# uTCA_Tongue3.net
KiCad netlist of a schematic drawn in Altium Designer
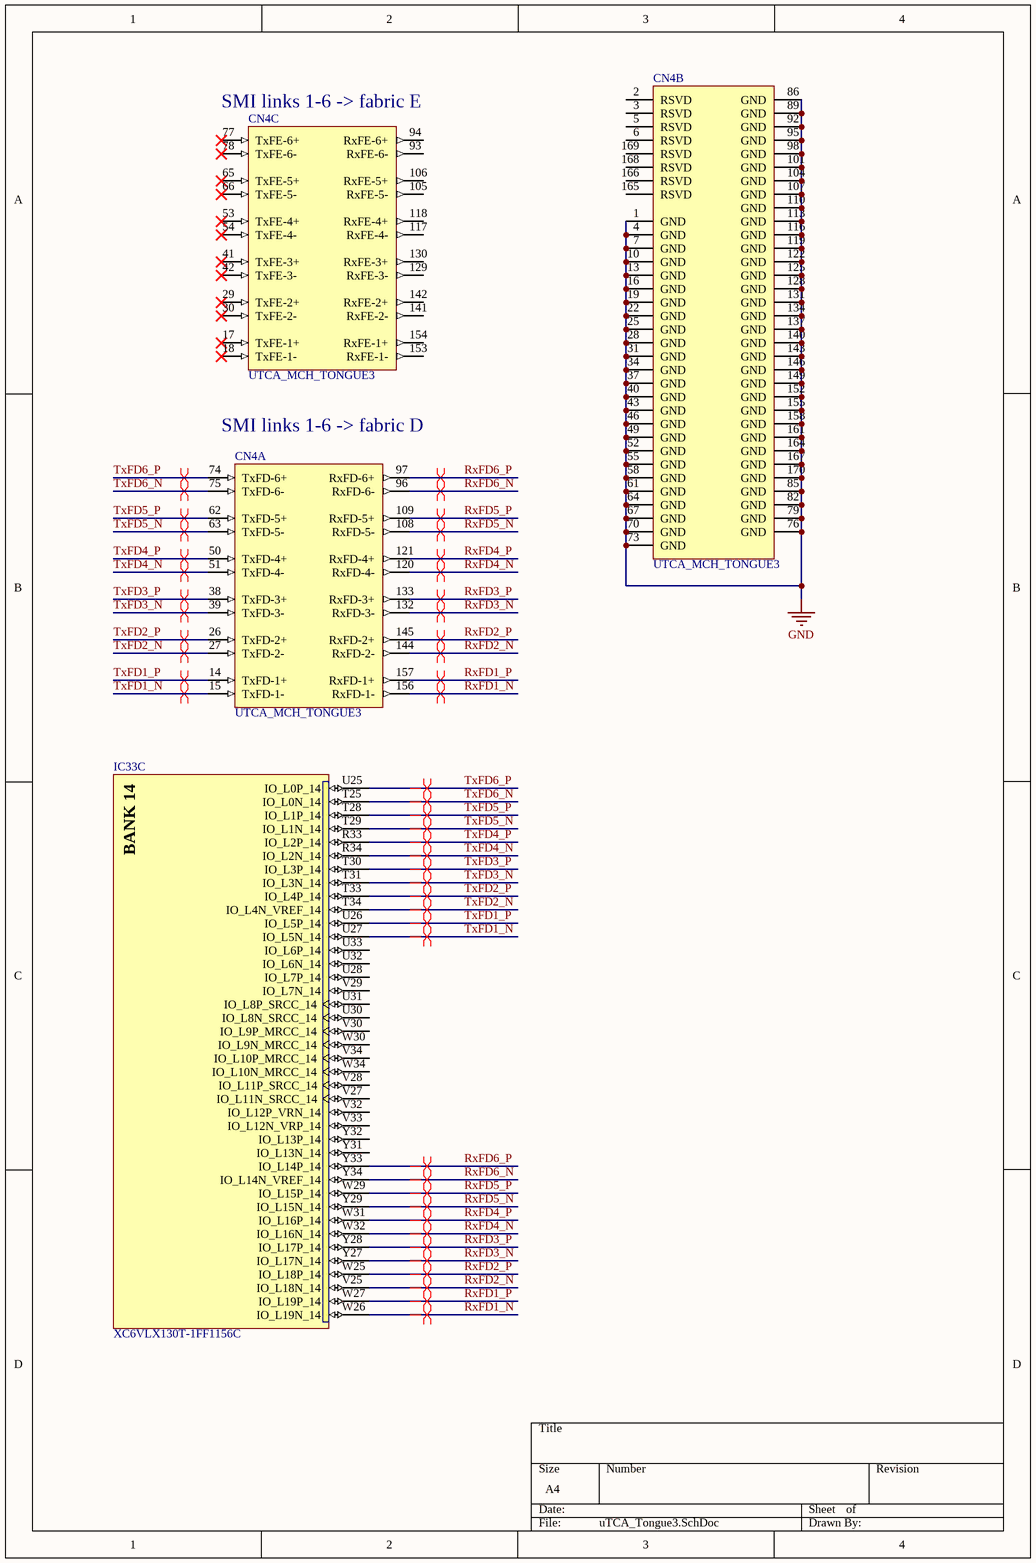
[diagram p0: uTCA_Tongue3.SchDoc]

(export (version "E")
  (design (tool "Eeschema 10.0.6"))
  (components
    (comp (ref "CN4")
      (value "UTCA_MCH_TONGUE3")
      (footprint "UTCA_MCH_TONGUE2_3_4")
      (description "microTCA MTCA.0 standard MCH connector 3")
      (libsource (lib "wr_switch") (part "UTCA_MCH_TONGUE3"))
    )
    (comp (ref "IC33")
      (value "XC6VLX130T-1FF1156C")
      (footprint "FF1156")
      (fields (field (name "PUBLISHER") "Altium Limited"))
      (libsource (lib "Xilinx Virtex-6") (part "XC6VLX130T-1FF1156C"))
    )
  )
  (nets
    (net (code "1") (name "/RxFD1_N") (class "Default")
      (node (ref "CN4") (pin "156") (pinfunction "RxFD-1-_156") (pintype "output"))
      (node (ref "IC33") (pin "W26") (pinfunction "IO_L19N_14_W26") (pintype "bidirectional"))
    )
    (net (code "2") (name "/RxFD1_P") (class "Default")
      (node (ref "CN4") (pin "157") (pinfunction "RxFD-1+_157") (pintype "output"))
      (node (ref "IC33") (pin "W27") (pinfunction "IO_L19P_14_W27") (pintype "bidirectional"))
    )
    (net (code "3") (name "/RxFD2_N") (class "Default")
      (node (ref "CN4") (pin "144") (pinfunction "RxFD-2-_144") (pintype "output"))
      (node (ref "IC33") (pin "V25") (pinfunction "IO_L18N_14_V25") (pintype "bidirectional"))
    )
    (net (code "4") (name "/RxFD2_P") (class "Default")
      (node (ref "CN4") (pin "145") (pinfunction "RxFD-2+_145") (pintype "output"))
      (node (ref "IC33") (pin "W25") (pinfunction "IO_L18P_14_W25") (pintype "bidirectional"))
    )
    (net (code "5") (name "/RxFD3_N") (class "Default")
      (node (ref "CN4") (pin "132") (pinfunction "RxFD-3-_132") (pintype "output"))
      (node (ref "IC33") (pin "Y27") (pinfunction "IO_L17N_14_Y27") (pintype "bidirectional"))
    )
    (net (code "6") (name "/RxFD3_P") (class "Default")
      (node (ref "CN4") (pin "133") (pinfunction "RxFD-3+_133") (pintype "output"))
      (node (ref "IC33") (pin "Y28") (pinfunction "IO_L17P_14_Y28") (pintype "bidirectional"))
    )
    (net (code "7") (name "/RxFD4_N") (class "Default")
      (node (ref "CN4") (pin "120") (pinfunction "RxFD-4-_120") (pintype "output"))
      (node (ref "IC33") (pin "W32") (pinfunction "IO_L16N_14_W32") (pintype "bidirectional"))
    )
    (net (code "8") (name "/RxFD4_P") (class "Default")
      (node (ref "CN4") (pin "121") (pinfunction "RxFD-4+_121") (pintype "output"))
      (node (ref "IC33") (pin "W31") (pinfunction "IO_L16P_14_W31") (pintype "bidirectional"))
    )
    (net (code "9") (name "/RxFD5_N") (class "Default")
      (node (ref "CN4") (pin "108") (pinfunction "RxFD-5-_108") (pintype "output"))
      (node (ref "IC33") (pin "Y29") (pinfunction "IO_L15N_14_Y29") (pintype "bidirectional"))
    )
    (net (code "10") (name "/RxFD5_P") (class "Default")
      (node (ref "CN4") (pin "109") (pinfunction "RxFD-5+_109") (pintype "output"))
      (node (ref "IC33") (pin "W29") (pinfunction "IO_L15P_14_W29") (pintype "bidirectional"))
    )
    (net (code "11") (name "/RxFD6_N") (class "Default")
      (node (ref "CN4") (pin "96") (pinfunction "RxFD-6-_96") (pintype "output"))
      (node (ref "IC33") (pin "Y34") (pinfunction "IO_L14N_VREF_14_Y34") (pintype "bidirectional"))
    )
    (net (code "12") (name "/RxFD6_P") (class "Default")
      (node (ref "CN4") (pin "97") (pinfunction "RxFD-6+_97") (pintype "output"))
      (node (ref "IC33") (pin "Y33") (pinfunction "IO_L14P_14_Y33") (pintype "bidirectional"))
    )
    (net (code "13") (name "/TxFD1_N") (class "Default")
      (node (ref "CN4") (pin "15") (pinfunction "TxFD-1-_15") (pintype "input"))
      (node (ref "IC33") (pin "U27") (pinfunction "IO_L5N_14_U27") (pintype "bidirectional"))
    )
    (net (code "14") (name "/TxFD1_P") (class "Default")
      (node (ref "CN4") (pin "14") (pinfunction "TxFD-1+_14") (pintype "input"))
      (node (ref "IC33") (pin "U26") (pinfunction "IO_L5P_14_U26") (pintype "bidirectional"))
    )
    (net (code "15") (name "/TxFD2_N") (class "Default")
      (node (ref "CN4") (pin "27") (pinfunction "TxFD-2-_27") (pintype "input"))
      (node (ref "IC33") (pin "T34") (pinfunction "IO_L4N_VREF_14_T34") (pintype "bidirectional"))
    )
    (net (code "16") (name "/TxFD2_P") (class "Default")
      (node (ref "CN4") (pin "26") (pinfunction "TxFD-2+_26") (pintype "input"))
      (node (ref "IC33") (pin "T33") (pinfunction "IO_L4P_14_T33") (pintype "bidirectional"))
    )
    (net (code "17") (name "/TxFD3_N") (class "Default")
      (node (ref "CN4") (pin "39") (pinfunction "TxFD-3-_39") (pintype "input"))
      (node (ref "IC33") (pin "T31") (pinfunction "IO_L3N_14_T31") (pintype "bidirectional"))
    )
    (net (code "18") (name "/TxFD3_P") (class "Default")
      (node (ref "CN4") (pin "38") (pinfunction "TxFD-3+_38") (pintype "input"))
      (node (ref "IC33") (pin "T30") (pinfunction "IO_L3P_14_T30") (pintype "bidirectional"))
    )
    (net (code "19") (name "/TxFD4_N") (class "Default")
      (node (ref "CN4") (pin "51") (pinfunction "TxFD-4-_51") (pintype "input"))
      (node (ref "IC33") (pin "R34") (pinfunction "IO_L2N_14_R34") (pintype "bidirectional"))
    )
    (net (code "20") (name "/TxFD4_P") (class "Default")
      (node (ref "CN4") (pin "50") (pinfunction "TxFD-4+_50") (pintype "input"))
      (node (ref "IC33") (pin "R33") (pinfunction "IO_L2P_14_R33") (pintype "bidirectional"))
    )
    (net (code "21") (name "/TxFD5_N") (class "Default")
      (node (ref "CN4") (pin "63") (pinfunction "TxFD-5-_63") (pintype "input"))
      (node (ref "IC33") (pin "T29") (pinfunction "IO_L1N_14_T29") (pintype "bidirectional"))
    )
    (net (code "22") (name "/TxFD5_P") (class "Default")
      (node (ref "CN4") (pin "62") (pinfunction "TxFD-5+_62") (pintype "input"))
      (node (ref "IC33") (pin "T28") (pinfunction "IO_L1P_14_T28") (pintype "bidirectional"))
    )
    (net (code "23") (name "/TxFD6_N") (class "Default")
      (node (ref "CN4") (pin "75") (pinfunction "TxFD-6-_75") (pintype "input"))
      (node (ref "IC33") (pin "T25") (pinfunction "IO_L0N_14_T25") (pintype "bidirectional"))
    )
    (net (code "24") (name "/TxFD6_P") (class "Default")
      (node (ref "CN4") (pin "74") (pinfunction "TxFD-6+_74") (pintype "input"))
      (node (ref "IC33") (pin "U25") (pinfunction "IO_L0P_14_U25") (pintype "bidirectional"))
    )
    (net (code "25") (name "GND") (class "Default")
      (node (ref "CN4") (pin "1") (pinfunction "GND_1") (pintype "power_in"))
      (node (ref "CN4") (pin "10") (pinfunction "GND_10") (pintype "power_in"))
      (node (ref "CN4") (pin "101") (pinfunction "GND_101") (pintype "power_in"))
      (node (ref "CN4") (pin "104") (pinfunction "GND_104") (pintype "power_in"))
      (node (ref "CN4") (pin "107") (pinfunction "GND_107") (pintype "power_in"))
      (node (ref "CN4") (pin "110") (pinfunction "GND_110") (pintype "power_in"))
      (node (ref "CN4") (pin "113") (pinfunction "GND_113") (pintype "power_in"))
      (node (ref "CN4") (pin "116") (pinfunction "GND_116") (pintype "power_in"))
      (node (ref "CN4") (pin "119") (pinfunction "GND_119") (pintype "power_in"))
      (node (ref "CN4") (pin "122") (pinfunction "GND_122") (pintype "power_in"))
      (node (ref "CN4") (pin "125") (pinfunction "GND_125") (pintype "power_in"))
      (node (ref "CN4") (pin "128") (pinfunction "GND_128") (pintype "power_in"))
      (node (ref "CN4") (pin "13") (pinfunction "GND_13") (pintype "power_in"))
      (node (ref "CN4") (pin "131") (pinfunction "GND_131") (pintype "power_in"))
      (node (ref "CN4") (pin "134") (pinfunction "GND_134") (pintype "power_in"))
      (node (ref "CN4") (pin "137") (pinfunction "GND_137") (pintype "power_in"))
      (node (ref "CN4") (pin "140") (pinfunction "GND_140") (pintype "power_in"))
      (node (ref "CN4") (pin "143") (pinfunction "GND_143") (pintype "power_in"))
      (node (ref "CN4") (pin "146") (pinfunction "GND_146") (pintype "power_in"))
      (node (ref "CN4") (pin "149") (pinfunction "GND_149") (pintype "power_in"))
      (node (ref "CN4") (pin "152") (pinfunction "GND_152") (pintype "power_in"))
      (node (ref "CN4") (pin "155") (pinfunction "GND_155") (pintype "power_in"))
      (node (ref "CN4") (pin "158") (pinfunction "GND_158") (pintype "power_in"))
      (node (ref "CN4") (pin "16") (pinfunction "GND_16") (pintype "power_in"))
      (node (ref "CN4") (pin "161") (pinfunction "GND_161") (pintype "power_in"))
      (node (ref "CN4") (pin "164") (pinfunction "GND_164") (pintype "power_in"))
      (node (ref "CN4") (pin "167") (pinfunction "GND_167") (pintype "power_in"))
      (node (ref "CN4") (pin "170") (pinfunction "GND_170") (pintype "power_in"))
      (node (ref "CN4") (pin "19") (pinfunction "GND_19") (pintype "power_in"))
      (node (ref "CN4") (pin "22") (pinfunction "GND_22") (pintype "power_in"))
      (node (ref "CN4") (pin "25") (pinfunction "GND_25") (pintype "power_in"))
      (node (ref "CN4") (pin "28") (pinfunction "GND_28") (pintype "power_in"))
      (node (ref "CN4") (pin "31") (pinfunction "GND_31") (pintype "power_in"))
      (node (ref "CN4") (pin "34") (pinfunction "GND_34") (pintype "power_in"))
      (node (ref "CN4") (pin "37") (pinfunction "GND_37") (pintype "power_in"))
      (node (ref "CN4") (pin "4") (pinfunction "GND_4") (pintype "power_in"))
      (node (ref "CN4") (pin "40") (pinfunction "GND_40") (pintype "power_in"))
      (node (ref "CN4") (pin "43") (pinfunction "GND_43") (pintype "power_in"))
      (node (ref "CN4") (pin "46") (pinfunction "GND_46") (pintype "power_in"))
      (node (ref "CN4") (pin "49") (pinfunction "GND_49") (pintype "power_in"))
      (node (ref "CN4") (pin "52") (pinfunction "GND_52") (pintype "power_in"))
      (node (ref "CN4") (pin "55") (pinfunction "GND_55") (pintype "power_in"))
      (node (ref "CN4") (pin "58") (pinfunction "GND_58") (pintype "power_in"))
      (node (ref "CN4") (pin "61") (pinfunction "GND_61") (pintype "power_in"))
      (node (ref "CN4") (pin "64") (pinfunction "GND_64") (pintype "power_in"))
      (node (ref "CN4") (pin "67") (pinfunction "GND_67") (pintype "power_in"))
      (node (ref "CN4") (pin "7") (pinfunction "GND_7") (pintype "power_in"))
      (node (ref "CN4") (pin "70") (pinfunction "GND_70") (pintype "power_in"))
      (node (ref "CN4") (pin "73") (pinfunction "GND_73") (pintype "power_in"))
      (node (ref "CN4") (pin "76") (pinfunction "GND_76") (pintype "power_in"))
      (node (ref "CN4") (pin "79") (pinfunction "GND_79") (pintype "power_in"))
      (node (ref "CN4") (pin "82") (pinfunction "GND_82") (pintype "power_in"))
      (node (ref "CN4") (pin "85") (pinfunction "GND_85") (pintype "power_in"))
      (node (ref "CN4") (pin "86") (pinfunction "GND_86") (pintype "power_in"))
      (node (ref "CN4") (pin "89") (pinfunction "GND_89") (pintype "power_in"))
      (node (ref "CN4") (pin "92") (pinfunction "GND_92") (pintype "power_in"))
      (node (ref "CN4") (pin "95") (pinfunction "GND_95") (pintype "power_in"))
      (node (ref "CN4") (pin "98") (pinfunction "GND_98") (pintype "power_in"))
    )
    (net (code "26") (name "unconnected-(CN4B-RSVD-Pad2)") (class "Default")
      (node (ref "CN4") (pin "2") (pinfunction "RSVD_2") (pintype "passive"))
    )
    (net (code "27") (name "unconnected-(CN4B-RSVD-Pad3)") (class "Default")
      (node (ref "CN4") (pin "3") (pinfunction "RSVD_3") (pintype "passive"))
    )
    (net (code "28") (name "unconnected-(CN4B-RSVD-Pad5)") (class "Default")
      (node (ref "CN4") (pin "5") (pinfunction "RSVD_5") (pintype "passive"))
    )
    (net (code "29") (name "unconnected-(CN4B-RSVD-Pad6)") (class "Default")
      (node (ref "CN4") (pin "6") (pinfunction "RSVD_6") (pintype "passive"))
    )
    (net (code "30") (name "unconnected-(CN4B-RSVD-Pad165)") (class "Default")
      (node (ref "CN4") (pin "165") (pinfunction "RSVD_165") (pintype "passive"))
    )
    (net (code "31") (name "unconnected-(CN4B-RSVD-Pad166)") (class "Default")
      (node (ref "CN4") (pin "166") (pinfunction "RSVD_166") (pintype "passive"))
    )
    (net (code "32") (name "unconnected-(CN4B-RSVD-Pad168)") (class "Default")
      (node (ref "CN4") (pin "168") (pinfunction "RSVD_168") (pintype "passive"))
    )
    (net (code "33") (name "unconnected-(CN4B-RSVD-Pad169)") (class "Default")
      (node (ref "CN4") (pin "169") (pinfunction "RSVD_169") (pintype "passive"))
    )
    (net (code "34") (name "unconnected-(CN4C-RxFE-1+-Pad154)") (class "Default")
      (node (ref "CN4") (pin "154") (pinfunction "RxFE-1+_154") (pintype "output"))
    )
    (net (code "35") (name "unconnected-(CN4C-RxFE-1--Pad153)") (class "Default")
      (node (ref "CN4") (pin "153") (pinfunction "RxFE-1-_153") (pintype "output"))
    )
    (net (code "36") (name "unconnected-(CN4C-RxFE-2+-Pad142)") (class "Default")
      (node (ref "CN4") (pin "142") (pinfunction "RxFE-2+_142") (pintype "output"))
    )
    (net (code "37") (name "unconnected-(CN4C-RxFE-2--Pad141)") (class "Default")
      (node (ref "CN4") (pin "141") (pinfunction "RxFE-2-_141") (pintype "output"))
    )
    (net (code "38") (name "unconnected-(CN4C-RxFE-3+-Pad130)") (class "Default")
      (node (ref "CN4") (pin "130") (pinfunction "RxFE-3+_130") (pintype "output"))
    )
    (net (code "39") (name "unconnected-(CN4C-RxFE-3--Pad129)") (class "Default")
      (node (ref "CN4") (pin "129") (pinfunction "RxFE-3-_129") (pintype "output"))
    )
    (net (code "40") (name "unconnected-(CN4C-RxFE-4+-Pad118)") (class "Default")
      (node (ref "CN4") (pin "118") (pinfunction "RxFE-4+_118") (pintype "output"))
    )
    (net (code "41") (name "unconnected-(CN4C-RxFE-4--Pad117)") (class "Default")
      (node (ref "CN4") (pin "117") (pinfunction "RxFE-4-_117") (pintype "output"))
    )
    (net (code "42") (name "unconnected-(CN4C-RxFE-5+-Pad106)") (class "Default")
      (node (ref "CN4") (pin "106") (pinfunction "RxFE-5+_106") (pintype "output"))
    )
    (net (code "43") (name "unconnected-(CN4C-RxFE-5--Pad105)") (class "Default")
      (node (ref "CN4") (pin "105") (pinfunction "RxFE-5-_105") (pintype "output"))
    )
    (net (code "44") (name "unconnected-(CN4C-RxFE-6+-Pad94)") (class "Default")
      (node (ref "CN4") (pin "94") (pinfunction "RxFE-6+_94") (pintype "output"))
    )
    (net (code "45") (name "unconnected-(CN4C-RxFE-6--Pad93)") (class "Default")
      (node (ref "CN4") (pin "93") (pinfunction "RxFE-6-_93") (pintype "output"))
    )
    (net (code "46") (name "unconnected-(CN4C-TxFE-1+-Pad17)") (class "Default")
      (node (ref "CN4") (pin "17") (pinfunction "TxFE-1+_17") (pintype "input+no_connect"))
    )
    (net (code "47") (name "unconnected-(CN4C-TxFE-1--Pad18)") (class "Default")
      (node (ref "CN4") (pin "18") (pinfunction "TxFE-1-_18") (pintype "input+no_connect"))
    )
    (net (code "48") (name "unconnected-(CN4C-TxFE-2+-Pad29)") (class "Default")
      (node (ref "CN4") (pin "29") (pinfunction "TxFE-2+_29") (pintype "input+no_connect"))
    )
    (net (code "49") (name "unconnected-(CN4C-TxFE-2--Pad30)") (class "Default")
      (node (ref "CN4") (pin "30") (pinfunction "TxFE-2-_30") (pintype "input+no_connect"))
    )
    (net (code "50") (name "unconnected-(CN4C-TxFE-3+-Pad41)") (class "Default")
      (node (ref "CN4") (pin "41") (pinfunction "TxFE-3+_41") (pintype "input+no_connect"))
    )
    (net (code "51") (name "unconnected-(CN4C-TxFE-3--Pad42)") (class "Default")
      (node (ref "CN4") (pin "42") (pinfunction "TxFE-3-_42") (pintype "input+no_connect"))
    )
    (net (code "52") (name "unconnected-(CN4C-TxFE-4+-Pad53)") (class "Default")
      (node (ref "CN4") (pin "53") (pinfunction "TxFE-4+_53") (pintype "input+no_connect"))
    )
    (net (code "53") (name "unconnected-(CN4C-TxFE-4--Pad54)") (class "Default")
      (node (ref "CN4") (pin "54") (pinfunction "TxFE-4-_54") (pintype "input+no_connect"))
    )
    (net (code "54") (name "unconnected-(CN4C-TxFE-5+-Pad65)") (class "Default")
      (node (ref "CN4") (pin "65") (pinfunction "TxFE-5+_65") (pintype "input+no_connect"))
    )
    (net (code "55") (name "unconnected-(CN4C-TxFE-5--Pad66)") (class "Default")
      (node (ref "CN4") (pin "66") (pinfunction "TxFE-5-_66") (pintype "input+no_connect"))
    )
    (net (code "56") (name "unconnected-(CN4C-TxFE-6+-Pad77)") (class "Default")
      (node (ref "CN4") (pin "77") (pinfunction "TxFE-6+_77") (pintype "input+no_connect"))
    )
    (net (code "57") (name "unconnected-(CN4C-TxFE-6--Pad78)") (class "Default")
      (node (ref "CN4") (pin "78") (pinfunction "TxFE-6-_78") (pintype "input+no_connect"))
    )
    (net (code "58") (name "unconnected-(IC33C-IO_L6N_14-PadU32)") (class "Default")
      (node (ref "IC33") (pin "U32") (pinfunction "IO_L6N_14_U32") (pintype "bidirectional"))
    )
    (net (code "59") (name "unconnected-(IC33C-IO_L6P_14-PadU33)") (class "Default")
      (node (ref "IC33") (pin "U33") (pinfunction "IO_L6P_14_U33") (pintype "bidirectional"))
    )
    (net (code "60") (name "unconnected-(IC33C-IO_L7N_14-PadV29)") (class "Default")
      (node (ref "IC33") (pin "V29") (pinfunction "IO_L7N_14_V29") (pintype "bidirectional"))
    )
    (net (code "61") (name "unconnected-(IC33C-IO_L7P_14-PadU28)") (class "Default")
      (node (ref "IC33") (pin "U28") (pinfunction "IO_L7P_14_U28") (pintype "bidirectional"))
    )
    (net (code "62") (name "unconnected-(IC33C-IO_L8N_SRCC_14-PadU30)") (class "Default")
      (node (ref "IC33") (pin "U30") (pinfunction "IO_L8N_SRCC_14_U30") (pintype "bidirectional"))
    )
    (net (code "63") (name "unconnected-(IC33C-IO_L8P_SRCC_14-PadU31)") (class "Default")
      (node (ref "IC33") (pin "U31") (pinfunction "IO_L8P_SRCC_14_U31") (pintype "bidirectional"))
    )
    (net (code "64") (name "unconnected-(IC33C-IO_L9N_MRCC_14-PadW30)") (class "Default")
      (node (ref "IC33") (pin "W30") (pinfunction "IO_L9N_MRCC_14_W30") (pintype "bidirectional"))
    )
    (net (code "65") (name "unconnected-(IC33C-IO_L9P_MRCC_14-PadV30)") (class "Default")
      (node (ref "IC33") (pin "V30") (pinfunction "IO_L9P_MRCC_14_V30") (pintype "bidirectional"))
    )
    (net (code "66") (name "unconnected-(IC33C-IO_L10N_MRCC_14-PadW34)") (class "Default")
      (node (ref "IC33") (pin "W34") (pinfunction "IO_L10N_MRCC_14_W34") (pintype "bidirectional"))
    )
    (net (code "67") (name "unconnected-(IC33C-IO_L10P_MRCC_14-PadV34)") (class "Default")
      (node (ref "IC33") (pin "V34") (pinfunction "IO_L10P_MRCC_14_V34") (pintype "bidirectional"))
    )
    (net (code "68") (name "unconnected-(IC33C-IO_L11N_SRCC_14-PadV27)") (class "Default")
      (node (ref "IC33") (pin "V27") (pinfunction "IO_L11N_SRCC_14_V27") (pintype "bidirectional"))
    )
    (net (code "69") (name "unconnected-(IC33C-IO_L11P_SRCC_14-PadV28)") (class "Default")
      (node (ref "IC33") (pin "V28") (pinfunction "IO_L11P_SRCC_14_V28") (pintype "bidirectional"))
    )
    (net (code "70") (name "unconnected-(IC33C-IO_L12N_VRP_14-PadV33)") (class "Default")
      (node (ref "IC33") (pin "V33") (pinfunction "IO_L12N_VRP_14_V33") (pintype "bidirectional"))
    )
    (net (code "71") (name "unconnected-(IC33C-IO_L12P_VRN_14-PadV32)") (class "Default")
      (node (ref "IC33") (pin "V32") (pinfunction "IO_L12P_VRN_14_V32") (pintype "bidirectional"))
    )
    (net (code "72") (name "unconnected-(IC33C-IO_L13N_14-PadY31)") (class "Default")
      (node (ref "IC33") (pin "Y31") (pinfunction "IO_L13N_14_Y31") (pintype "bidirectional"))
    )
    (net (code "73") (name "unconnected-(IC33C-IO_L13P_14-PadY32)") (class "Default")
      (node (ref "IC33") (pin "Y32") (pinfunction "IO_L13P_14_Y32") (pintype "bidirectional"))
    )
  )
)
